# Arduino_R3_Template.net
KiCad netlist of a schematic drawn in EAGLE
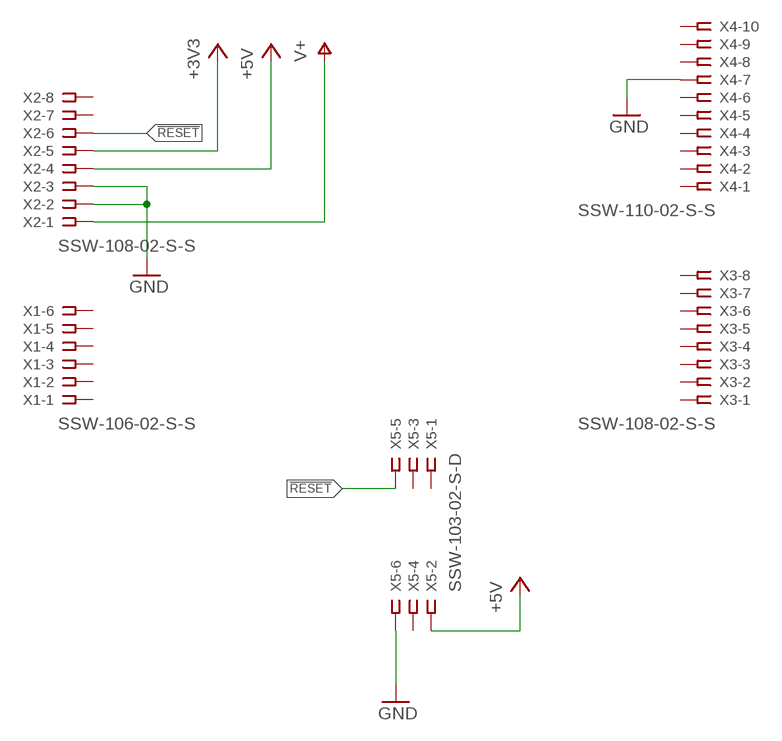
[diagram p0: schematic, sheet 1]

(export (version "E")
  (design (tool "Eeschema 10.0.6"))
  (components
    (comp (ref "X1")
      (value "SSW-106-02-S-S")
      (footprint "eagle-import:SSW-106-02-S-S")
      (libsource (lib "eagle-import") (part "SSW-106-02-S-S"))
    )
    (comp (ref "X2")
      (value "SSW-108-02-S-S")
      (footprint "eagle-import:SSW-108-02-S-S")
      (libsource (lib "eagle-import") (part "SSW-108-02-S-S"))
    )
    (comp (ref "X3")
      (value "SSW-108-02-S-S")
      (footprint "eagle-import:SSW-108-02-S-S")
      (libsource (lib "eagle-import") (part "SSW-108-02-S-S"))
    )
    (comp (ref "X4")
      (value "SSW-110-02-S-S")
      (footprint "eagle-import:SSW-110-02-S-S")
      (libsource (lib "eagle-import") (part "SSW-110-02-S-S"))
    )
    (comp (ref "X5")
      (value "SSW-103-02-S-D")
      (footprint "eagle-import:SSW-103-02-S-D")
      (libsource (lib "eagle-import") (part "SSW-103-02-S-D"))
    )
  )
  (nets
    (net (code "1") (name "+3V3") (class "Default")
      (node (ref "X2") (pin "5") (pinfunction "1_5") (pintype "passive"))
    )
    (net (code "2") (name "+5V") (class "Default")
      (node (ref "X2") (pin "4") (pinfunction "1_4") (pintype "passive"))
      (node (ref "X5") (pin "2") (pinfunction "1_2") (pintype "passive"))
    )
    (net (code "3") (name "/~{RESET}") (class "Default")
      (node (ref "X2") (pin "6") (pinfunction "1_6") (pintype "passive"))
      (node (ref "X5") (pin "5") (pinfunction "1_5") (pintype "passive"))
    )
    (net (code "4") (name "GND") (class "Default")
      (node (ref "X2") (pin "2") (pinfunction "1_2") (pintype "passive"))
      (node (ref "X2") (pin "3") (pinfunction "1_3") (pintype "passive"))
      (node (ref "X4") (pin "7") (pinfunction "1_7") (pintype "passive"))
      (node (ref "X5") (pin "6") (pinfunction "1_6") (pintype "passive"))
    )
    (net (code "5") (name "V+") (class "Default")
      (node (ref "X2") (pin "1") (pinfunction "1_1") (pintype "passive"))
    )
    (net (code "6") (name "unconnected-(X1-Pad1)") (class "Default")
      (node (ref "X1") (pin "1") (pinfunction "1_1") (pintype "passive"))
    )
    (net (code "7") (name "unconnected-(X1B-1-Pad2)") (class "Default")
      (node (ref "X1") (pin "2") (pinfunction "1_2") (pintype "passive"))
    )
    (net (code "8") (name "unconnected-(X1C-1-Pad3)") (class "Default")
      (node (ref "X1") (pin "3") (pinfunction "1_3") (pintype "passive"))
    )
    (net (code "9") (name "unconnected-(X1D-1-Pad4)") (class "Default")
      (node (ref "X1") (pin "4") (pinfunction "1_4") (pintype "passive"))
    )
    (net (code "10") (name "unconnected-(X1E-1-Pad5)") (class "Default")
      (node (ref "X1") (pin "5") (pinfunction "1_5") (pintype "passive"))
    )
    (net (code "11") (name "unconnected-(X1F-1-Pad6)") (class "Default")
      (node (ref "X1") (pin "6") (pinfunction "1_6") (pintype "passive"))
    )
    (net (code "12") (name "unconnected-(X2G-1-Pad7)") (class "Default")
      (node (ref "X2") (pin "7") (pinfunction "1_7") (pintype "passive"))
    )
    (net (code "13") (name "unconnected-(X2H-1-Pad8)") (class "Default")
      (node (ref "X2") (pin "8") (pinfunction "1_8") (pintype "passive"))
    )
    (net (code "14") (name "unconnected-(X3-Pad1)") (class "Default")
      (node (ref "X3") (pin "1") (pinfunction "1_1") (pintype "passive"))
    )
    (net (code "15") (name "unconnected-(X3B-1-Pad2)") (class "Default")
      (node (ref "X3") (pin "2") (pinfunction "1_2") (pintype "passive"))
    )
    (net (code "16") (name "unconnected-(X3C-1-Pad3)") (class "Default")
      (node (ref "X3") (pin "3") (pinfunction "1_3") (pintype "passive"))
    )
    (net (code "17") (name "unconnected-(X3D-1-Pad4)") (class "Default")
      (node (ref "X3") (pin "4") (pinfunction "1_4") (pintype "passive"))
    )
    (net (code "18") (name "unconnected-(X3E-1-Pad5)") (class "Default")
      (node (ref "X3") (pin "5") (pinfunction "1_5") (pintype "passive"))
    )
    (net (code "19") (name "unconnected-(X3F-1-Pad6)") (class "Default")
      (node (ref "X3") (pin "6") (pinfunction "1_6") (pintype "passive"))
    )
    (net (code "20") (name "unconnected-(X3G-1-Pad7)") (class "Default")
      (node (ref "X3") (pin "7") (pinfunction "1_7") (pintype "passive"))
    )
    (net (code "21") (name "unconnected-(X3H-1-Pad8)") (class "Default")
      (node (ref "X3") (pin "8") (pinfunction "1_8") (pintype "passive"))
    )
    (net (code "22") (name "unconnected-(X4-Pad1)") (class "Default")
      (node (ref "X4") (pin "1") (pinfunction "1_1") (pintype "passive"))
    )
    (net (code "23") (name "unconnected-(X4B-1-Pad10)") (class "Default")
      (node (ref "X4") (pin "10") (pinfunction "1_10") (pintype "passive"))
    )
    (net (code "24") (name "unconnected-(X4C-1-Pad2)") (class "Default")
      (node (ref "X4") (pin "2") (pinfunction "1_2") (pintype "passive"))
    )
    (net (code "25") (name "unconnected-(X4D-1-Pad3)") (class "Default")
      (node (ref "X4") (pin "3") (pinfunction "1_3") (pintype "passive"))
    )
    (net (code "26") (name "unconnected-(X4E-1-Pad4)") (class "Default")
      (node (ref "X4") (pin "4") (pinfunction "1_4") (pintype "passive"))
    )
    (net (code "27") (name "unconnected-(X4F-1-Pad5)") (class "Default")
      (node (ref "X4") (pin "5") (pinfunction "1_5") (pintype "passive"))
    )
    (net (code "28") (name "unconnected-(X4G-1-Pad6)") (class "Default")
      (node (ref "X4") (pin "6") (pinfunction "1_6") (pintype "passive"))
    )
    (net (code "29") (name "unconnected-(X4I-1-Pad8)") (class "Default")
      (node (ref "X4") (pin "8") (pinfunction "1_8") (pintype "passive"))
    )
    (net (code "30") (name "unconnected-(X4J-1-Pad9)") (class "Default")
      (node (ref "X4") (pin "9") (pinfunction "1_9") (pintype "passive"))
    )
    (net (code "31") (name "unconnected-(X5-Pad1)") (class "Default")
      (node (ref "X5") (pin "1") (pinfunction "1_1") (pintype "passive"))
    )
    (net (code "32") (name "unconnected-(X5C-1-Pad3)") (class "Default")
      (node (ref "X5") (pin "3") (pinfunction "1_3") (pintype "passive"))
    )
    (net (code "33") (name "unconnected-(X5D-1-Pad4)") (class "Default")
      (node (ref "X5") (pin "4") (pinfunction "1_4") (pintype "passive"))
    )
  )
)
